# SCH_EASYEDA.net
KiCad netlist of a schematic drawn in EasyEDA
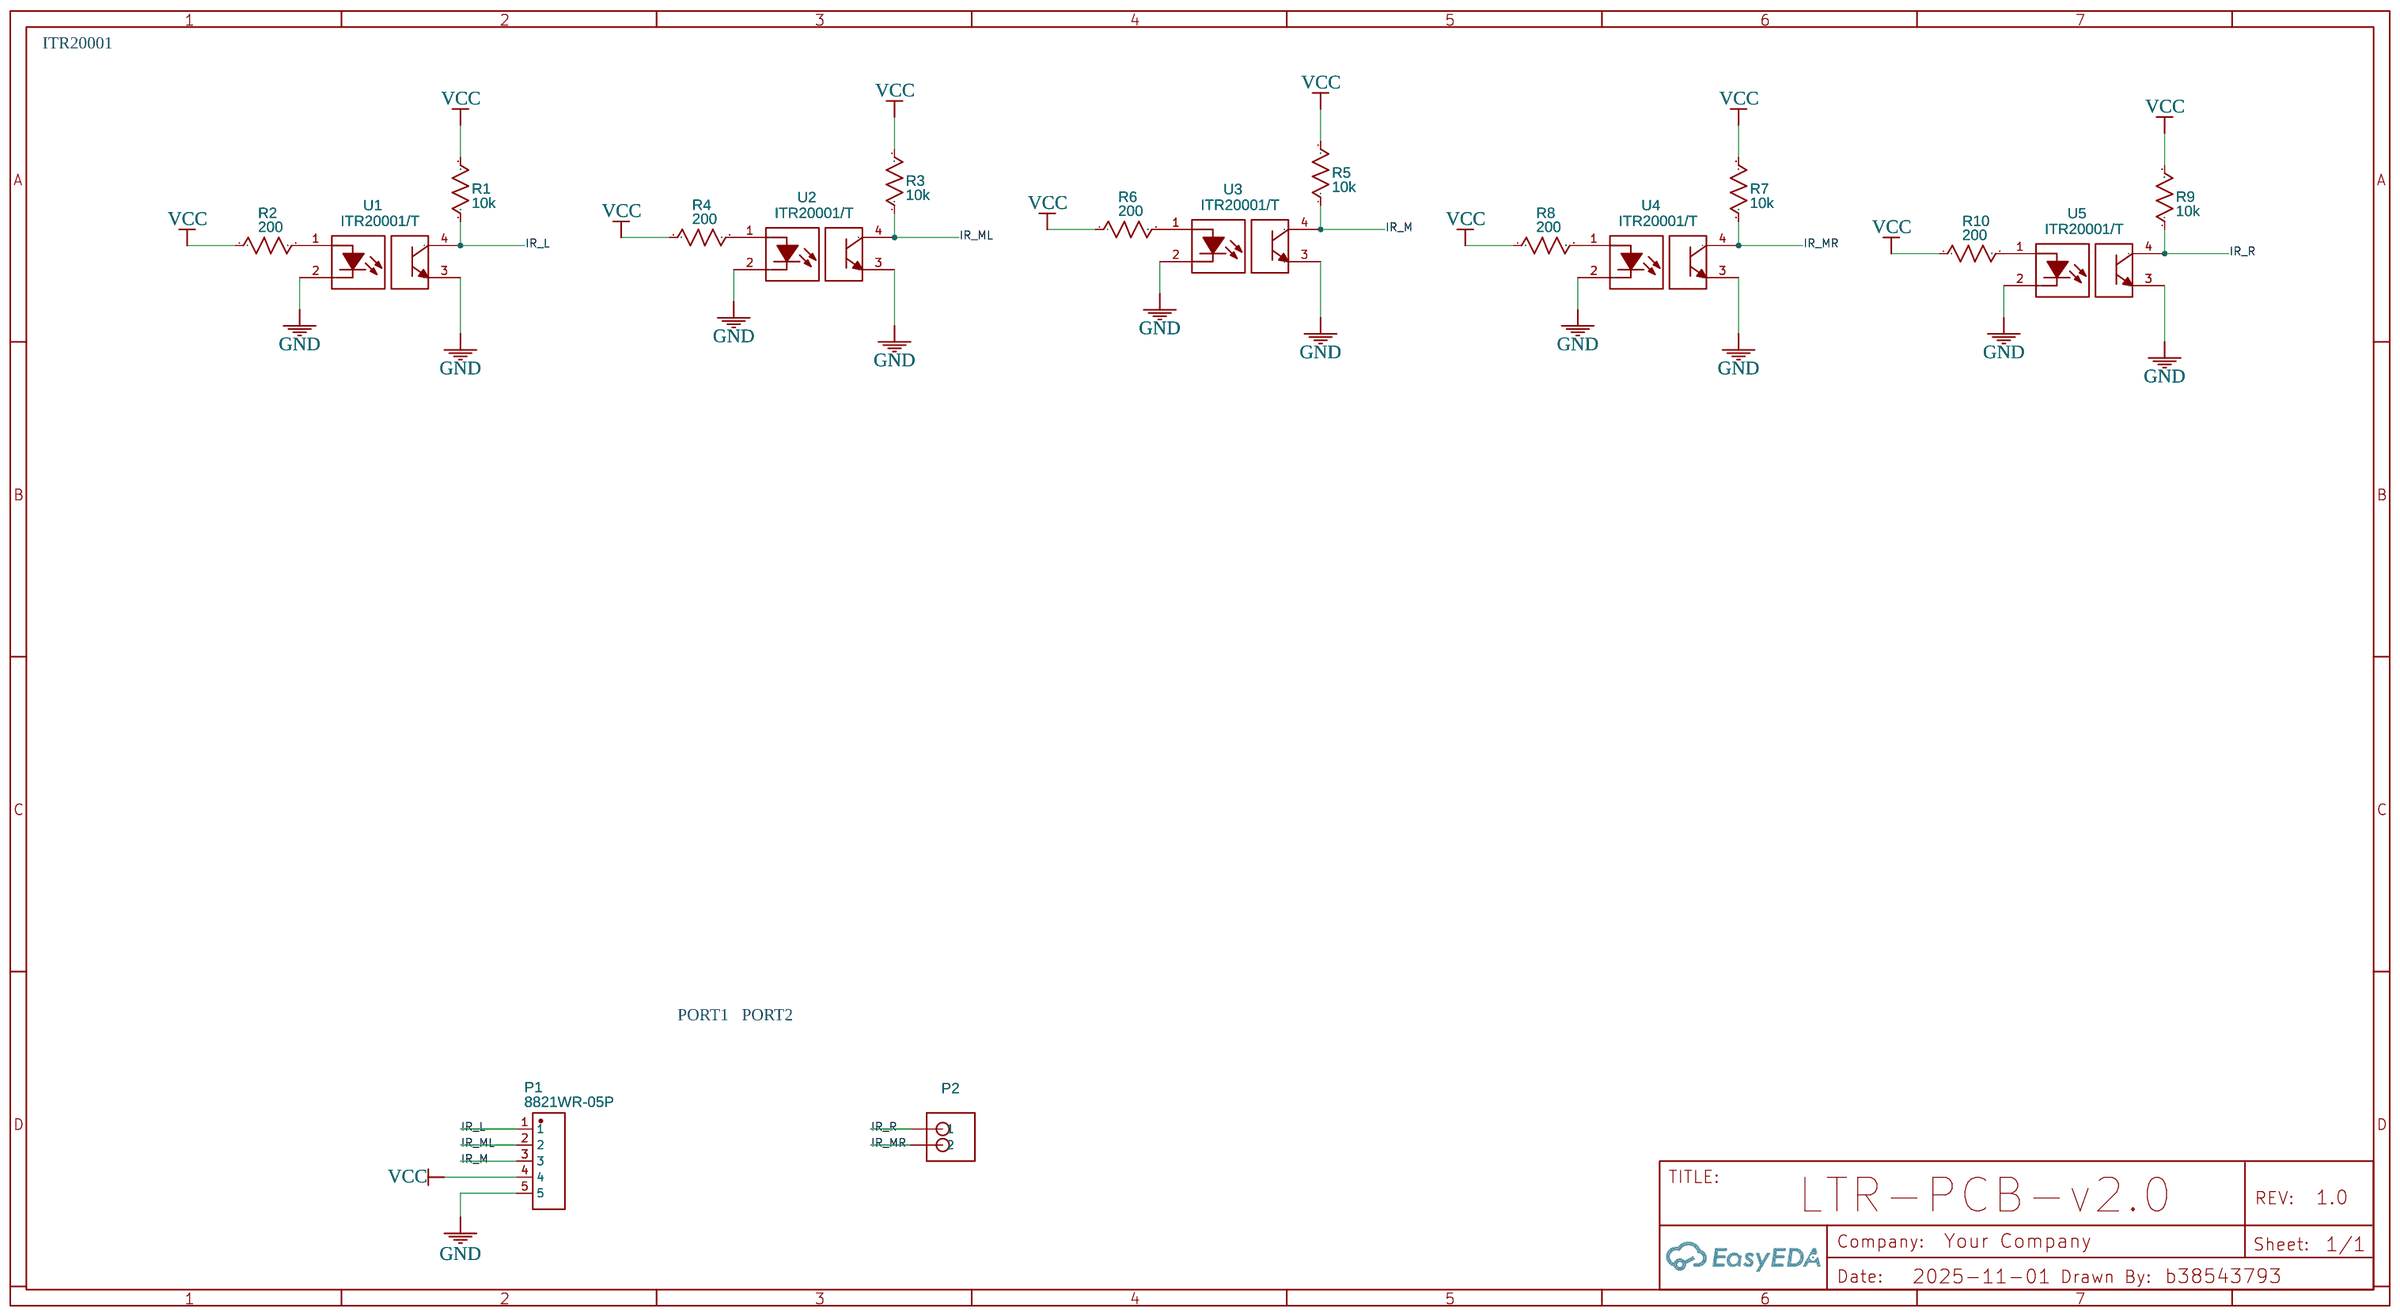
[diagram p0: schematic sheet]

(export (version "E")
  (design (tool "Eeschema 10.0.6"))
  (components
    (comp (ref "P1")
      (value "8821WR-05P")
      (fields (field (name "Manufacturer") "HanElectricity(瀚源)"))
      (libsource (lib "") (part "8821WR-05P"))
    )
    (comp (ref "P2") (value "JST-PH_2-PIN_HEADER") (libsource (lib "") (part "JST-PH_2-PIN_HEADER")))
    (comp (ref "R1") (value "10k") (libsource (lib "") (part "R_0603_US_1")))
    (comp (ref "R2") (value "200") (libsource (lib "") (part "R_0603_US")))
    (comp (ref "R3") (value "10k") (libsource (lib "") (part "R_0603_US_1")))
    (comp (ref "R4") (value "200") (libsource (lib "") (part "R_0603_US")))
    (comp (ref "R5") (value "10k") (libsource (lib "") (part "R_0603_US_1")))
    (comp (ref "R6") (value "200") (libsource (lib "") (part "R_0603_US")))
    (comp (ref "R7") (value "10k") (libsource (lib "") (part "R_0603_US_1")))
    (comp (ref "R8") (value "200") (libsource (lib "") (part "R_0603_US")))
    (comp (ref "R9") (value "10k") (libsource (lib "") (part "R_0603_US_1")))
    (comp (ref "R10") (value "200") (libsource (lib "") (part "R_0603_US")))
    (comp (ref "U1")
      (value "ITR20001/T")
      (fields (field (name "Manufacturer") "EVERLIGHT(亿光)"))
      (libsource (lib "") (part "ITR20001/T"))
    )
    (comp (ref "U2")
      (value "ITR20001/T")
      (fields (field (name "Manufacturer") "EVERLIGHT(亿光)"))
      (libsource (lib "") (part "ITR20001/T"))
    )
    (comp (ref "U3")
      (value "ITR20001/T")
      (fields (field (name "Manufacturer") "EVERLIGHT(亿光)"))
      (libsource (lib "") (part "ITR20001/T"))
    )
    (comp (ref "U4")
      (value "ITR20001/T")
      (fields (field (name "Manufacturer") "EVERLIGHT(亿光)"))
      (libsource (lib "") (part "ITR20001/T"))
    )
    (comp (ref "U5")
      (value "ITR20001/T")
      (fields (field (name "Manufacturer") "EVERLIGHT(亿光)"))
      (libsource (lib "") (part "ITR20001/T"))
    )
  )
  (nets
    (net (code "1") (name "/IR_L") (class "Default")
      (node (ref "P1") (pin "1") (pinfunction "1_1") (pintype "unspecified"))
      (node (ref "R1") (pin "1") (pinfunction "1_1") (pintype "unspecified"))
      (node (ref "U1") (pin "4") (pinfunction "4_4") (pintype "unspecified"))
    )
    (net (code "2") (name "/IR_M") (class "Default")
      (node (ref "P1") (pin "3") (pinfunction "3_3") (pintype "unspecified"))
      (node (ref "R5") (pin "1") (pinfunction "1_1") (pintype "unspecified"))
      (node (ref "U3") (pin "4") (pinfunction "4_4") (pintype "unspecified"))
    )
    (net (code "3") (name "/IR_ML") (class "Default")
      (node (ref "P1") (pin "2") (pinfunction "2_2") (pintype "unspecified"))
      (node (ref "R3") (pin "1") (pinfunction "1_1") (pintype "unspecified"))
      (node (ref "U2") (pin "4") (pinfunction "4_4") (pintype "unspecified"))
    )
    (net (code "4") (name "/IR_MR") (class "Default")
      (node (ref "P2") (pin "P2") (pinfunction "2_P2") (pintype "unspecified"))
      (node (ref "R7") (pin "1") (pinfunction "1_1") (pintype "unspecified"))
      (node (ref "U4") (pin "4") (pinfunction "4_4") (pintype "unspecified"))
    )
    (net (code "5") (name "/IR_R") (class "Default")
      (node (ref "P2") (pin "P1") (pinfunction "1_P1") (pintype "unspecified"))
      (node (ref "R9") (pin "1") (pinfunction "1_1") (pintype "unspecified"))
      (node (ref "U5") (pin "4") (pinfunction "4_4") (pintype "unspecified"))
    )
    (net (code "6") (name "GND") (class "Default")
      (node (ref "P1") (pin "5") (pinfunction "5_5") (pintype "unspecified"))
      (node (ref "U1") (pin "2") (pinfunction "2_2") (pintype "unspecified"))
      (node (ref "U1") (pin "3") (pinfunction "3_3") (pintype "unspecified"))
      (node (ref "U2") (pin "2") (pinfunction "2_2") (pintype "unspecified"))
      (node (ref "U2") (pin "3") (pinfunction "3_3") (pintype "unspecified"))
      (node (ref "U3") (pin "2") (pinfunction "2_2") (pintype "unspecified"))
      (node (ref "U3") (pin "3") (pinfunction "3_3") (pintype "unspecified"))
      (node (ref "U4") (pin "2") (pinfunction "2_2") (pintype "unspecified"))
      (node (ref "U4") (pin "3") (pinfunction "3_3") (pintype "unspecified"))
      (node (ref "U5") (pin "2") (pinfunction "2_2") (pintype "unspecified"))
      (node (ref "U5") (pin "3") (pinfunction "3_3") (pintype "unspecified"))
    )
    (net (code "7") (name "Net-(R2-Pad2)") (class "Default")
      (node (ref "R2") (pin "2") (pinfunction "2_2") (pintype "unspecified"))
      (node (ref "U1") (pin "1") (pinfunction "1_1") (pintype "unspecified"))
    )
    (net (code "8") (name "Net-(R4-Pad2)") (class "Default")
      (node (ref "R4") (pin "2") (pinfunction "2_2") (pintype "unspecified"))
      (node (ref "U2") (pin "1") (pinfunction "1_1") (pintype "unspecified"))
    )
    (net (code "9") (name "Net-(R6-Pad2)") (class "Default")
      (node (ref "R6") (pin "2") (pinfunction "2_2") (pintype "unspecified"))
      (node (ref "U3") (pin "1") (pinfunction "1_1") (pintype "unspecified"))
    )
    (net (code "10") (name "Net-(R8-Pad2)") (class "Default")
      (node (ref "R8") (pin "2") (pinfunction "2_2") (pintype "unspecified"))
      (node (ref "U4") (pin "1") (pinfunction "1_1") (pintype "unspecified"))
    )
    (net (code "11") (name "Net-(R10-Pad2)") (class "Default")
      (node (ref "R10") (pin "2") (pinfunction "2_2") (pintype "unspecified"))
      (node (ref "U5") (pin "1") (pinfunction "1_1") (pintype "unspecified"))
    )
    (net (code "12") (name "VCC") (class "Default")
      (node (ref "P1") (pin "4") (pinfunction "4_4") (pintype "unspecified"))
      (node (ref "R1") (pin "2") (pinfunction "2_2") (pintype "unspecified"))
      (node (ref "R10") (pin "1") (pinfunction "1_1") (pintype "unspecified"))
      (node (ref "R2") (pin "1") (pinfunction "1_1") (pintype "unspecified"))
      (node (ref "R3") (pin "2") (pinfunction "2_2") (pintype "unspecified"))
      (node (ref "R4") (pin "1") (pinfunction "1_1") (pintype "unspecified"))
      (node (ref "R5") (pin "2") (pinfunction "2_2") (pintype "unspecified"))
      (node (ref "R6") (pin "1") (pinfunction "1_1") (pintype "unspecified"))
      (node (ref "R7") (pin "2") (pinfunction "2_2") (pintype "unspecified"))
      (node (ref "R8") (pin "1") (pinfunction "1_1") (pintype "unspecified"))
      (node (ref "R9") (pin "2") (pinfunction "2_2") (pintype "unspecified"))
    )
  )
)
